# usb_input.net
KiCad netlist of a schematic drawn in Altium Designer
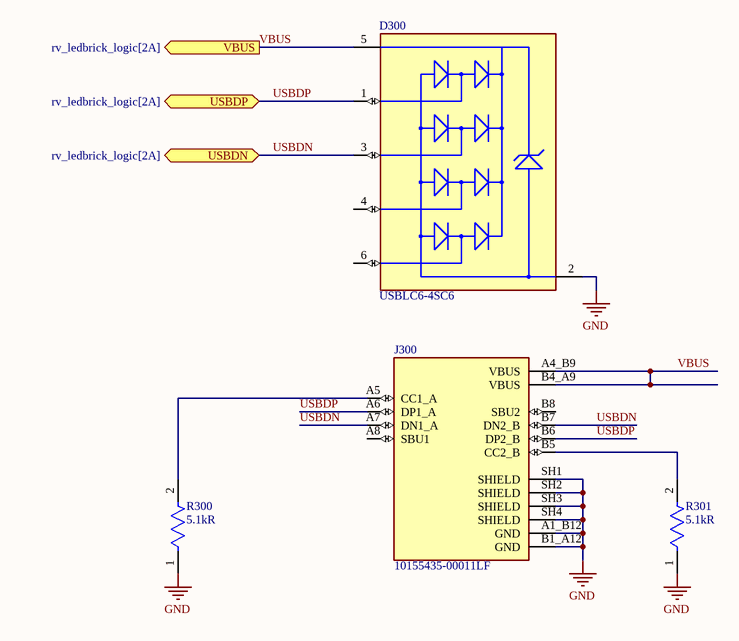
[diagram p0: usb_input.SchDoc]

(export (version "E")
  (design (tool "Eeschema 10.0.6"))
  (components
    (comp (ref "D300")
      (value "USBLC6-4SC6")
      (footprint "FP-SOT23-6L-MFG")
      (description "ESD Suppressor 15KV 6-Pin SOT-23 T/R - Product that comes on tape, but is not reeled")
      (libsource (lib "StackFoundry LLC") (part "3e70b616ccdc4c88b528e1820c4a7da"))
    )
    (comp (ref "J300")
      (value "10155435-00011LF")
      (footprint "AMPHENOL_10155435-00011LF")
      (description "16 Position 5 A USB Right Angle Receptacle Connector")
      (fields (field (name "MF") "Amphenol ICC (FCI)"))
      (libsource (lib "StackFoundry LLC") (part "10155435-00011LF"))
    )
    (comp (ref "R300")
      (value "5.1kR")
      (footprint "FP-AC0402-IPC_A")
      (description "SMD Chip Resistor, 5.1 kOhm, ± 1%, 63 mW, 0402 [1005 Metric], Thick Film, General Purpose")
      (fields (field (name "TOLERANCE") "1%") (field (name "Comment") "AC0402FR-075K1L"))
      (libsource (lib "StackFoundry LLC") (part "1029c3af85768c4190bb7ad29bc67b5"))
    )
    (comp (ref "R301")
      (value "5.1kR")
      (footprint "FP-AC0402-IPC_A")
      (description "SMD Chip Resistor, 5.1 kOhm, ± 1%, 63 mW, 0402 [1005 Metric], Thick Film, General Purpose")
      (fields (field (name "TOLERANCE") "1%") (field (name "Comment") "AC0402FR-075K1L"))
      (libsource (lib "StackFoundry LLC") (part "1029c3af85768c4190bb7ad29bc67b5"))
    )
  )
  (nets
    (net (code "1") (name "/USBDN") (class "Default")
      (node (ref "D300") (pin "3") (pinfunction "I/O2_3") (pintype "bidirectional"))
      (node (ref "J300") (pin "A7") (pinfunction "DN1_A_A7") (pintype "bidirectional"))
      (node (ref "J300") (pin "B7") (pinfunction "DN2_B_B7") (pintype "bidirectional"))
    )
    (net (code "2") (name "/USBDP") (class "Default")
      (node (ref "D300") (pin "1") (pinfunction "I/O1_1") (pintype "bidirectional"))
      (node (ref "J300") (pin "A6") (pinfunction "DP1_A_A6") (pintype "bidirectional"))
      (node (ref "J300") (pin "B6") (pinfunction "DP2_B_B6") (pintype "bidirectional"))
    )
    (net (code "3") (name "/VBUS") (class "Default")
      (node (ref "D300") (pin "5") (pinfunction "VBUS_5") (pintype "power_in"))
      (node (ref "J300") (pin "A4_B9") (pinfunction "VBUS_A4_B9") (pintype "power_in"))
      (node (ref "J300") (pin "B4_A9") (pinfunction "VBUS_B4_A9") (pintype "power_in"))
    )
    (net (code "4") (name "GND") (class "Default")
      (node (ref "D300") (pin "2") (pinfunction "GND_2") (pintype "power_in"))
      (node (ref "J300") (pin "A1_B12") (pinfunction "GND_A1_B12") (pintype "power_in"))
      (node (ref "J300") (pin "B1_A12") (pinfunction "GND_B1_A12") (pintype "power_in"))
      (node (ref "J300") (pin "SH1") (pinfunction "SHIELD_SH1") (pintype "passive"))
      (node (ref "J300") (pin "SH2") (pinfunction "SHIELD_SH2") (pintype "passive"))
      (node (ref "J300") (pin "SH3") (pinfunction "SHIELD_SH3") (pintype "passive"))
      (node (ref "J300") (pin "SH4") (pinfunction "SHIELD_SH4") (pintype "passive"))
      (node (ref "R300") (pin "1") (pinfunction "1_1") (pintype "passive"))
      (node (ref "R301") (pin "1") (pinfunction "1_1") (pintype "passive"))
    )
    (net (code "5") (name "Net-(J300-CC1_A)") (class "Default")
      (node (ref "J300") (pin "A5") (pinfunction "CC1_A_A5") (pintype "bidirectional"))
      (node (ref "R300") (pin "2") (pinfunction "2_2") (pintype "passive"))
    )
    (net (code "6") (name "Net-(J300-CC2_B)") (class "Default")
      (node (ref "J300") (pin "B5") (pinfunction "CC2_B_B5") (pintype "bidirectional"))
      (node (ref "R301") (pin "2") (pinfunction "2_2") (pintype "passive"))
    )
    (net (code "7") (name "unconnected-(D300-I{slash}O3-Pad4)") (class "Default")
      (node (ref "D300") (pin "4") (pinfunction "I/O3_4") (pintype "bidirectional"))
    )
    (net (code "8") (name "unconnected-(D300-I{slash}O4-Pad6)") (class "Default")
      (node (ref "D300") (pin "6") (pinfunction "I/O4_6") (pintype "bidirectional"))
    )
    (net (code "9") (name "unconnected-(J300-SBU1-PadA8)") (class "Default")
      (node (ref "J300") (pin "A8") (pinfunction "SBU1_A8") (pintype "bidirectional"))
    )
    (net (code "10") (name "unconnected-(J300-SBU2-PadB8)") (class "Default")
      (node (ref "J300") (pin "B8") (pinfunction "SBU2_B8") (pintype "bidirectional"))
    )
  )
)
